# MicroStudent.net
KiCad netlist of a schematic drawn in Altium Designer
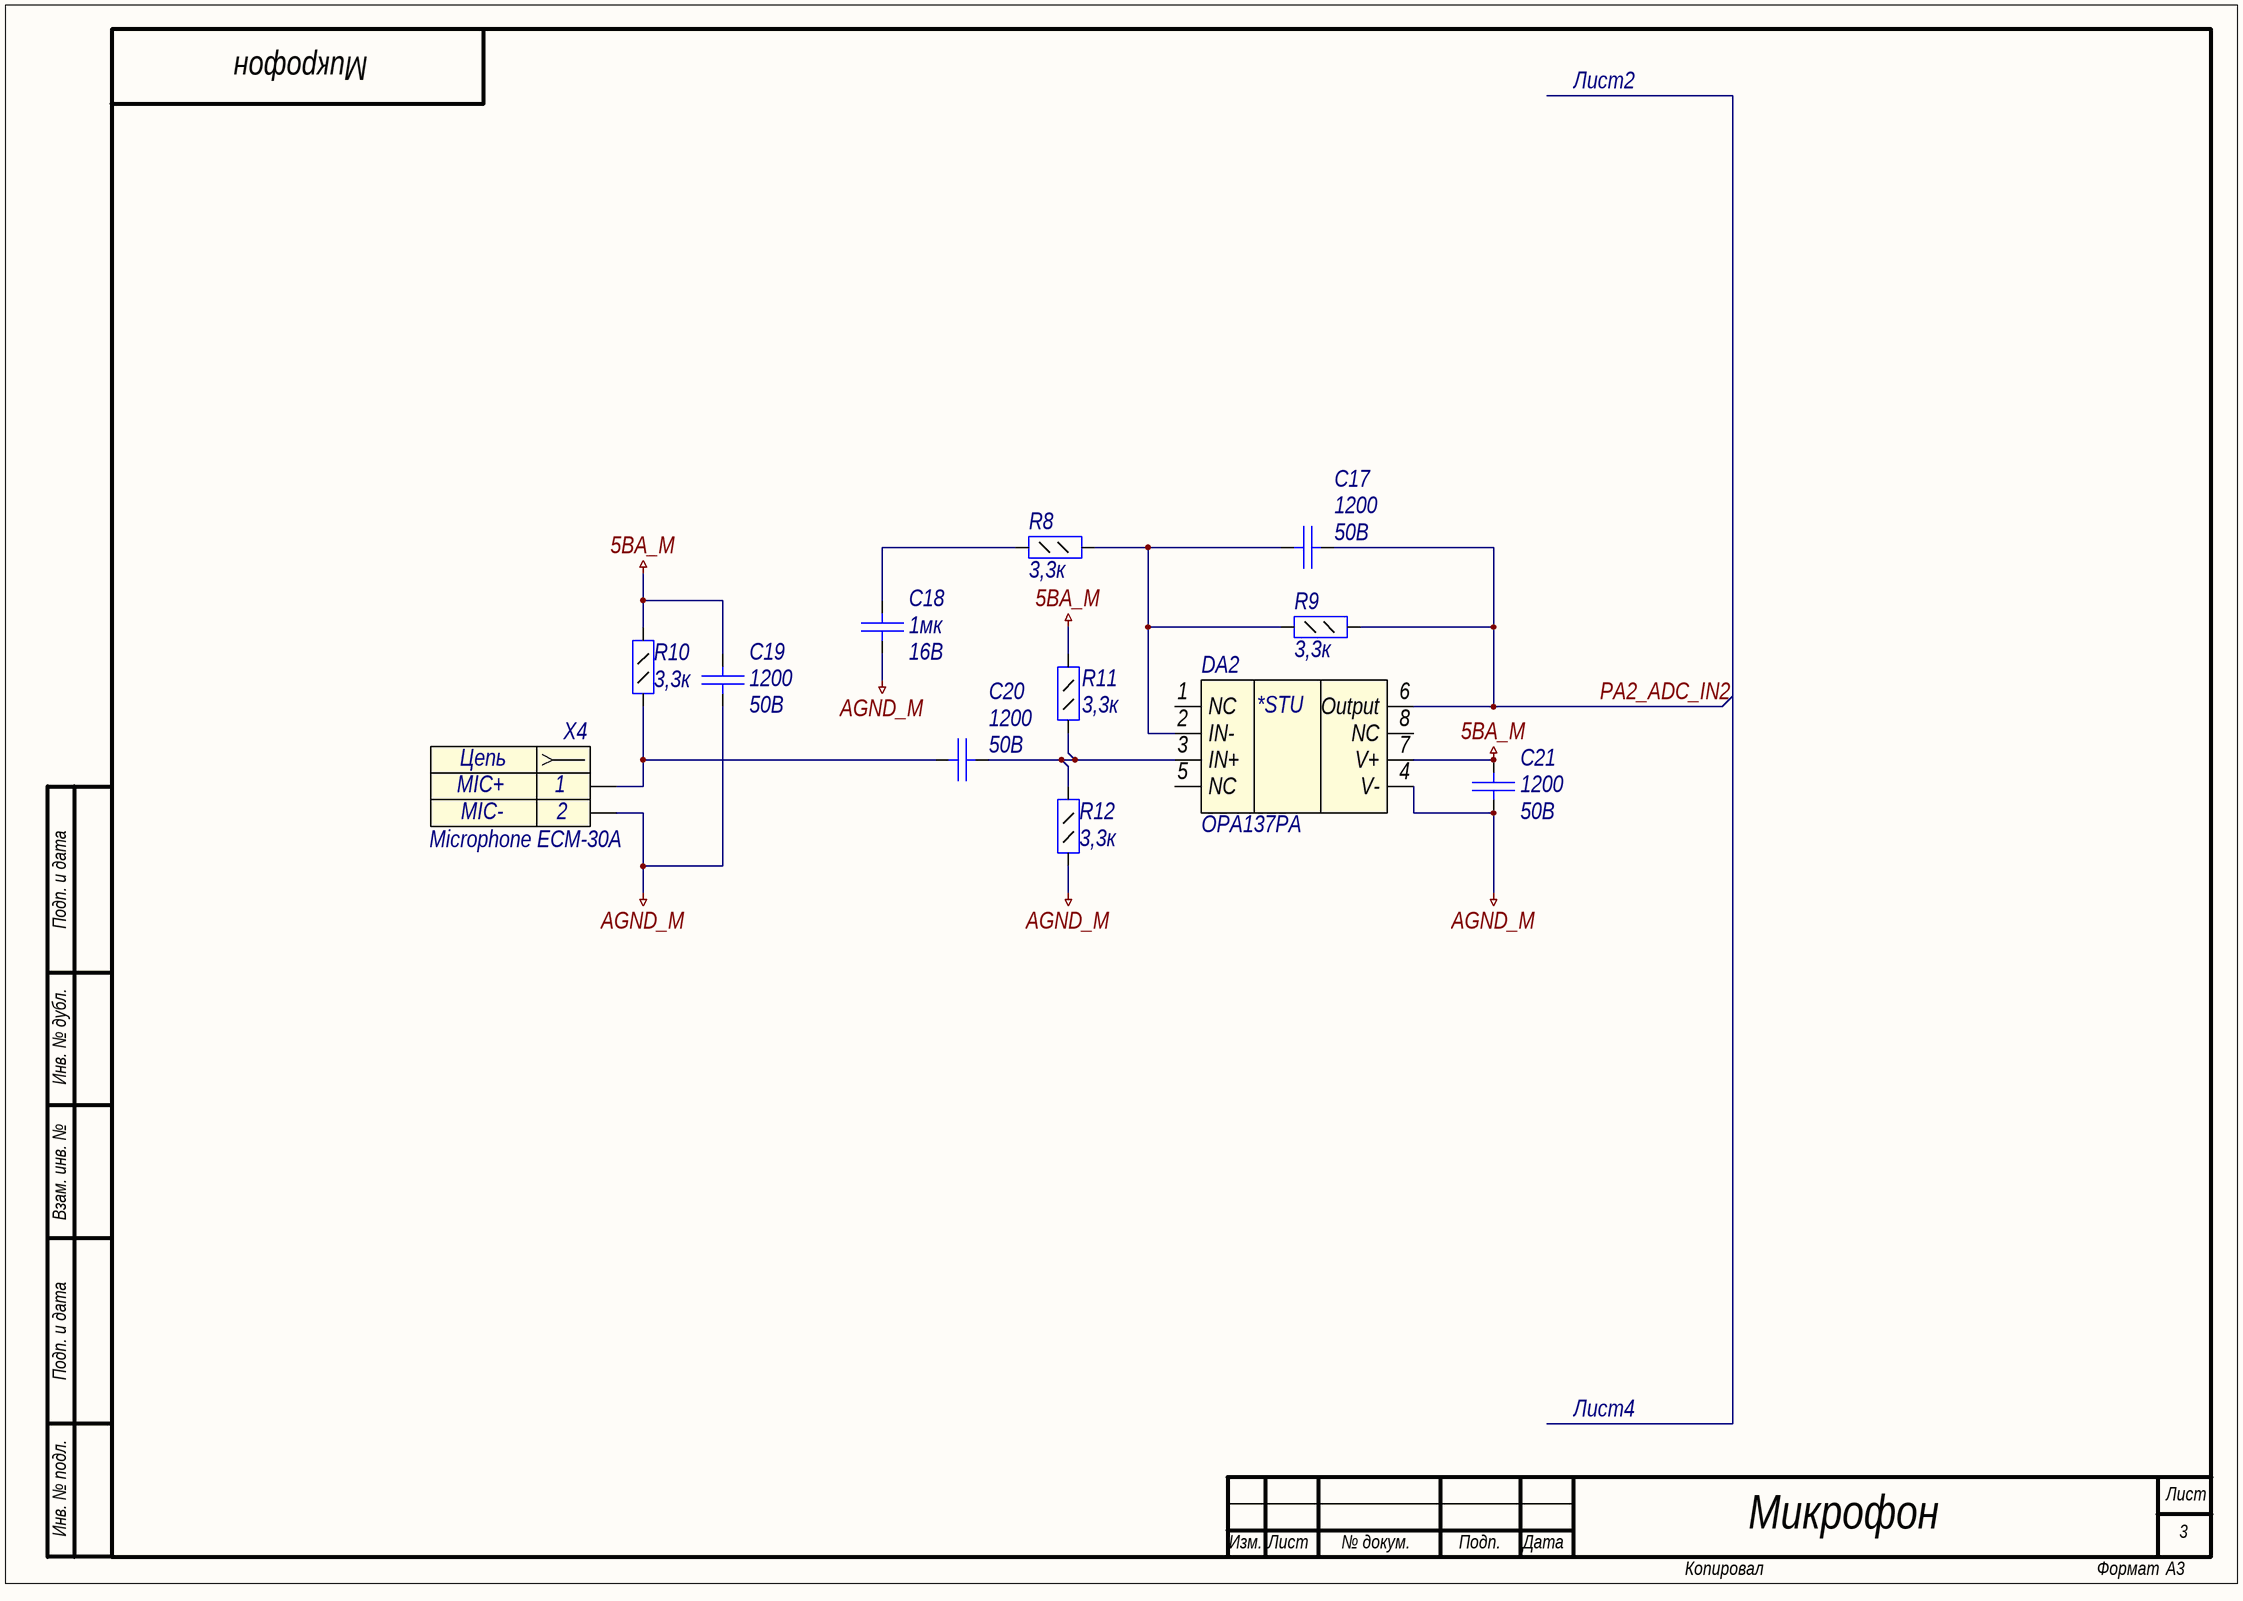
[diagram p0: MicroStudent.SchDoc]

(export (version "E")
  (design (tool "Eeschema 10.0.6"))
  (components
    (comp (ref "C17")
      (value "1200")
      (footprint "C0805")
      (description "Конденсатор")
      (fields
        (field (name "VOLTAGE") "50В")
        (field (name "PART NUMBER") "GRM216R71H122K")
        (field (name "Comment") "Capacitor")
      )
      (libsource (lib "MOP44") (part "Capacitor"))
    )
    (comp (ref "C18")
      (value "1мк")
      (footprint "C0805")
      (description "Конденсатор")
      (fields
        (field (name "VOLTAGE") "16B")
        (field (name "PART NUMBER") "GRM21BR71C105K")
        (field (name "Comment") "Capacitor")
      )
      (libsource (lib "MOP44") (part "Capacitor"))
    )
    (comp (ref "C19")
      (value "1200")
      (footprint "C0805")
      (description "Конденсатор")
      (fields
        (field (name "VOLTAGE") "50В")
        (field (name "PART NUMBER") "GRM216R71H122K")
        (field (name "Comment") "Capacitor")
      )
      (libsource (lib "MOP44") (part "Capacitor"))
    )
    (comp (ref "C20")
      (value "1200")
      (footprint "C0805")
      (description "Конденсатор")
      (fields
        (field (name "VOLTAGE") "50В")
        (field (name "PART NUMBER") "GRM216R71H122K")
        (field (name "Comment") "Capacitor")
      )
      (libsource (lib "MOP44") (part "Capacitor"))
    )
    (comp (ref "C21")
      (value "1200")
      (footprint "C0805")
      (description "Конденсатор")
      (fields
        (field (name "VOLTAGE") "50В")
        (field (name "PART NUMBER") "GRM216R71H122K")
        (field (name "Comment") "Capacitor")
      )
      (libsource (lib "MOP44") (part "Capacitor"))
    )
    (comp (ref "DA2")
      (value "OPA137PA")
      (footprint "DIP8")
      (description "FET-INPUT OPERATIONAL AMPLIFIERS")
      (fields (field (name "PART NUMBER") "OPA137PA"))
      (libsource (lib "MOP44") (part "OPA137PA"))
    )
    (comp (ref "R8")
      (value "3,3к")
      (footprint "R0805")
      (description "Резистор")
      (fields (field (name "POWER") "0,125Вт") (field (name "PART NUMBER") "RC0805FR-072K3"))
      (libsource (lib "MOP44") (part "Resistor_0,125Вт"))
    )
    (comp (ref "R9")
      (value "3,3к")
      (footprint "R0805")
      (description "Резистор")
      (fields (field (name "POWER") "0,125Вт") (field (name "PART NUMBER") "RC0805FR-072K3"))
      (libsource (lib "MOP44") (part "Resistor_0,125Вт"))
    )
    (comp (ref "R10")
      (value "3,3к")
      (footprint "R0805")
      (description "Резистор")
      (fields (field (name "POWER") "0,125Вт") (field (name "PART NUMBER") "RC0805FR-072K3"))
      (libsource (lib "") (part "Resistor_0,125Вт_1"))
    )
    (comp (ref "R11")
      (value "3,3к")
      (footprint "R0805")
      (description "Резистор")
      (fields (field (name "POWER") "0,125Вт") (field (name "Comment") "Resistor_0,125Вт"))
      (libsource (lib "") (part "Resistor_0,125Вт_1"))
    )
    (comp (ref "R12")
      (value "3,3к")
      (footprint "R0805")
      (description "Резистор")
      (fields (field (name "POWER") "0,125Вт") (field (name "PART NUMBER") "RC0805FR-072K3"))
      (libsource (lib "") (part "Resistor_0,125Вт_1"))
    )
    (comp (ref "X4")
      (value "Microphone ECM-30A")
      (footprint "CWF-2R")
      (description "Разъем - 2 конт. розетка")
      (fields (field (name "PART NUMBER") "DS1069-2 MR-A"))
      (libsource (lib "MOP44") (part "Header_2_sct"))
    )
  )
  (nets
    (net (code "1") (name "/PA2_ADC_IN2") (class "Default")
      (node (ref "C17") (pin "1") (pinfunction "1_1") (pintype "passive"))
      (node (ref "DA2") (pin "6") (pinfunction "Output_6") (pintype "power_in"))
      (node (ref "R9") (pin "2") (pinfunction "2_2") (pintype "passive"))
    )
    (net (code "2") (name "5BA_M") (class "Default")
      (node (ref "C19") (pin "1") (pinfunction "1_1") (pintype "passive"))
      (node (ref "C21") (pin "1") (pinfunction "1_1") (pintype "passive"))
      (node (ref "DA2") (pin "7") (pinfunction "V+_7") (pintype "power_in"))
      (node (ref "R10") (pin "2") (pinfunction "2_2") (pintype "passive"))
      (node (ref "R11") (pin "2") (pinfunction "2_2") (pintype "passive"))
    )
    (net (code "3") (name "AGND_M") (class "Default")
      (node (ref "C18") (pin "1") (pinfunction "1_1") (pintype "passive"))
      (node (ref "C19") (pin "2") (pinfunction "2_2") (pintype "passive"))
      (node (ref "C21") (pin "2") (pinfunction "2_2") (pintype "passive"))
      (node (ref "DA2") (pin "4") (pinfunction "V-_4") (pintype "power_in"))
      (node (ref "R12") (pin "1") (pinfunction "1_1") (pintype "passive"))
      (node (ref "X4") (pin "2") (pinfunction "2_2") (pintype "passive"))
    )
    (net (code "4") (name "Net-(C18-Pad2)") (class "Default")
      (node (ref "C18") (pin "2") (pinfunction "2_2") (pintype "passive"))
      (node (ref "R8") (pin "1") (pinfunction "1_1") (pintype "passive"))
    )
    (net (code "5") (name "Net-(C20-Pad2)") (class "Default")
      (node (ref "C20") (pin "2") (pinfunction "2_2") (pintype "passive"))
      (node (ref "R10") (pin "1") (pinfunction "1_1") (pintype "passive"))
      (node (ref "X4") (pin "1") (pinfunction "1_1") (pintype "passive"))
    )
    (net (code "6") (name "Net-(DA2-IN+)") (class "Default")
      (node (ref "C20") (pin "1") (pinfunction "1_1") (pintype "passive"))
      (node (ref "DA2") (pin "3") (pinfunction "IN+_3") (pintype "power_in"))
      (node (ref "R11") (pin "1") (pinfunction "1_1") (pintype "passive"))
      (node (ref "R12") (pin "2") (pinfunction "2_2") (pintype "passive"))
    )
    (net (code "7") (name "Net-(DA2-IN-)") (class "Default")
      (node (ref "C17") (pin "2") (pinfunction "2_2") (pintype "passive"))
      (node (ref "DA2") (pin "2") (pinfunction "IN-_2") (pintype "power_in"))
      (node (ref "R8") (pin "2") (pinfunction "2_2") (pintype "passive"))
      (node (ref "R9") (pin "1") (pinfunction "1_1") (pintype "passive"))
    )
    (net (code "8") (name "unconnected-(DA2-NC-Pad1)") (class "Default")
      (node (ref "DA2") (pin "1") (pinfunction "NC_1") (pintype "power_in"))
    )
    (net (code "9") (name "unconnected-(DA2-NC-Pad5)") (class "Default")
      (node (ref "DA2") (pin "5") (pinfunction "NC_5") (pintype "power_in"))
    )
    (net (code "10") (name "unconnected-(DA2-NC-Pad8)") (class "Default")
      (node (ref "DA2") (pin "8") (pinfunction "NC_8") (pintype "power_in"))
    )
  )
)
